# LaserTagSMT.net
KiCad netlist of a schematic drawn in EAGLE
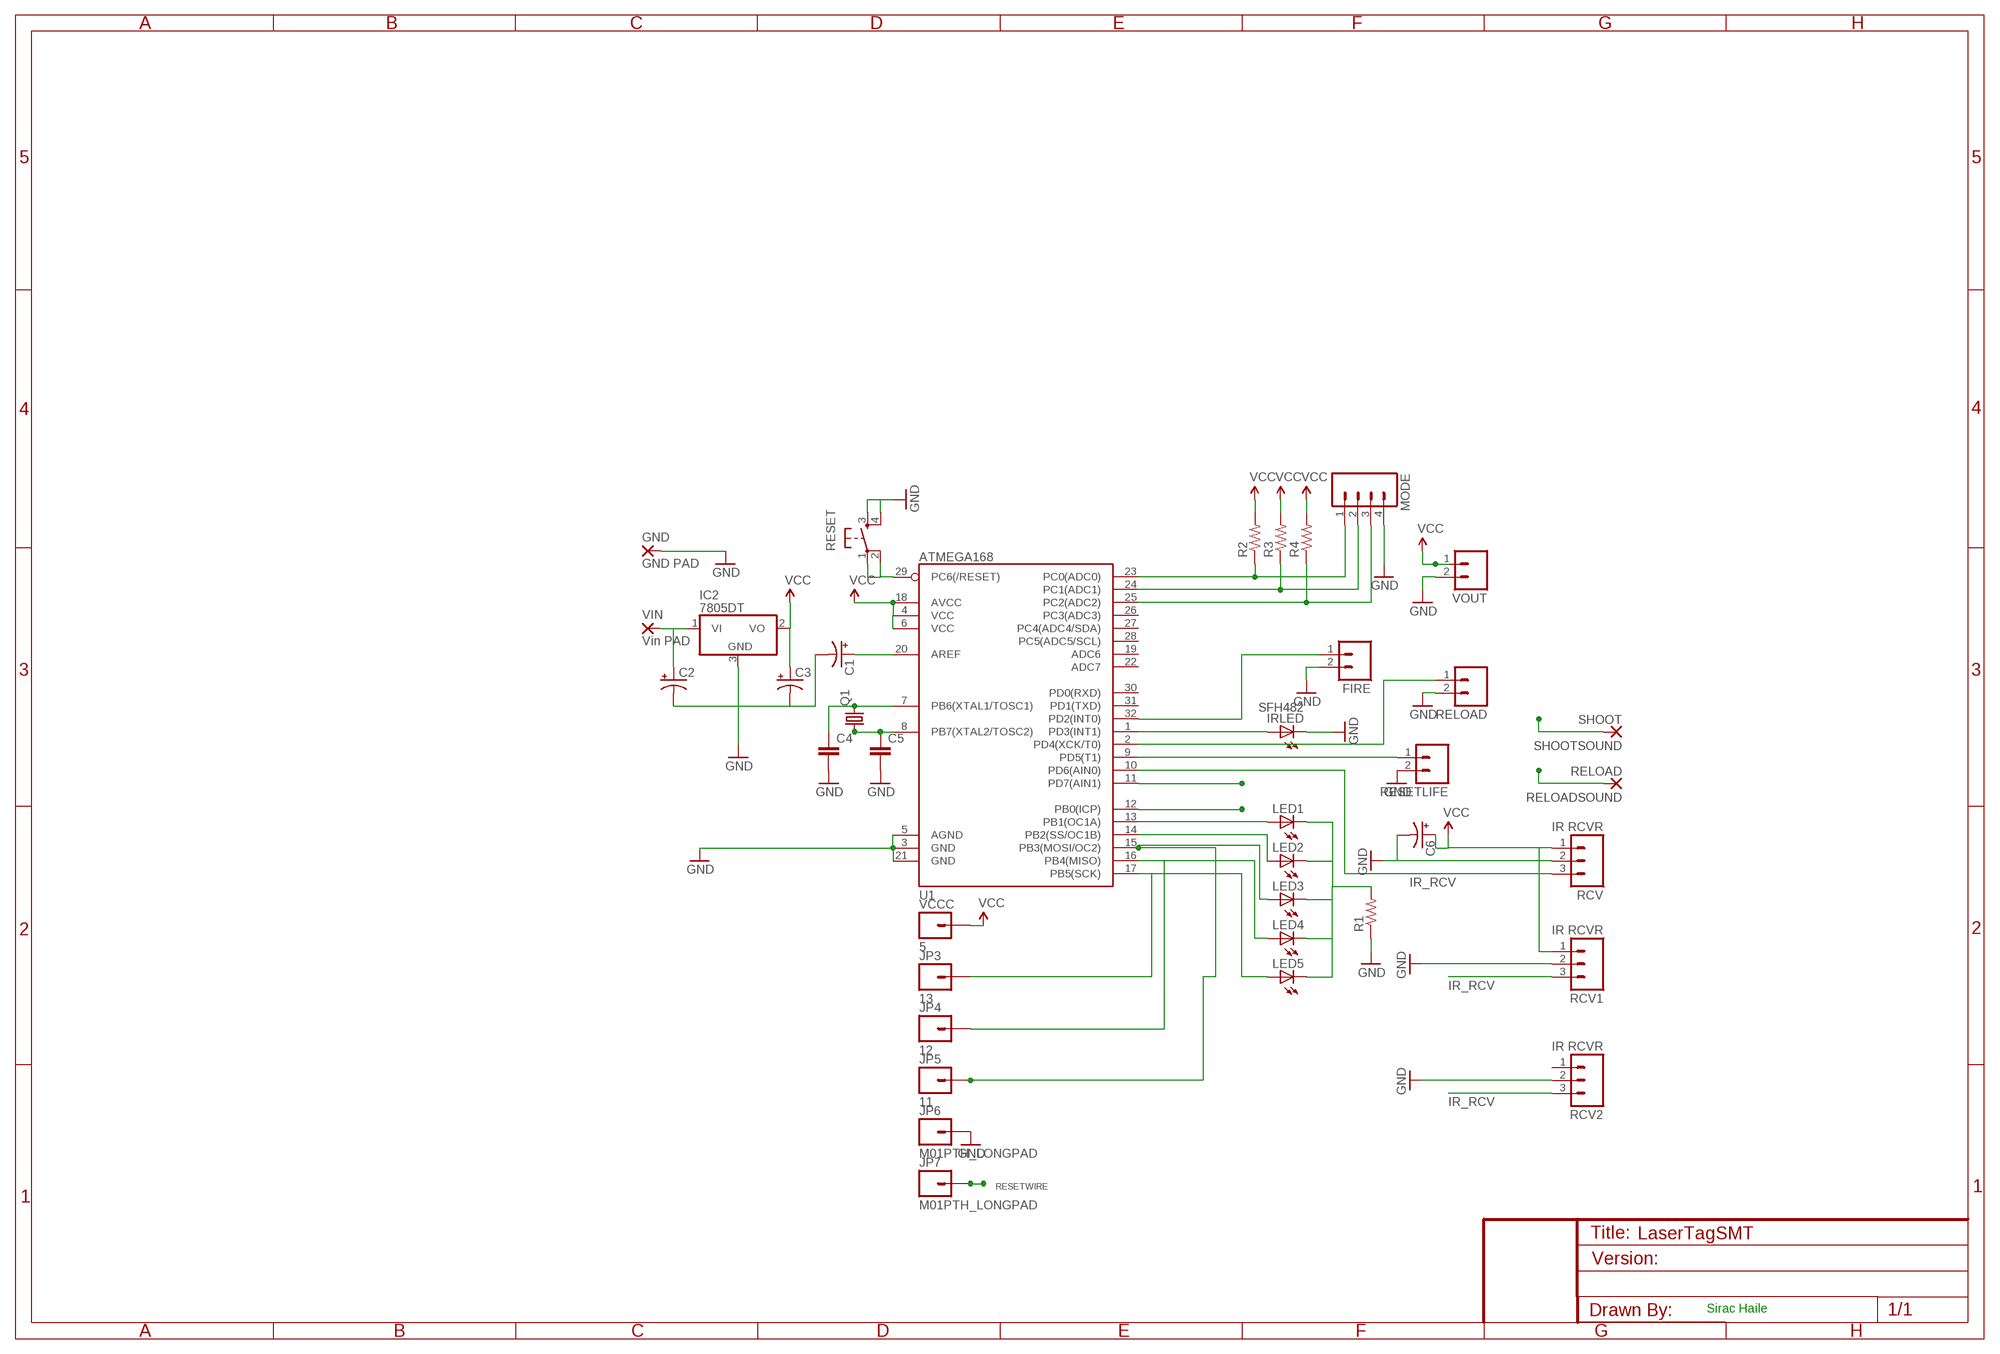
[diagram p0: schematic, sheet 1]

(export (version "E")
  (design (tool "Eeschema 10.0.6"))
  (components
    (comp (ref "C1")
      (value "CAP_POLPTH1")
      (footprint "eagle-import:CPOL-RADIAL-100UF-25V")
      (libsource (lib "eagle-import") (part "CAP_POLPTH1"))
    )
    (comp (ref "C2")
      (value "CAP_POLPTH1")
      (footprint "eagle-import:CPOL-RADIAL-100UF-25V")
      (libsource (lib "eagle-import") (part "CAP_POLPTH1"))
    )
    (comp (ref "C3")
      (value "CAP_POLPTH1")
      (footprint "eagle-import:CPOL-RADIAL-100UF-25V")
      (libsource (lib "eagle-import") (part "CAP_POLPTH1"))
    )
    (comp (ref "C4")
      (value "CAPEZ")
      (footprint "eagle-import:CAP-PTH-SMALLEZ")
      (libsource (lib "eagle-import") (part "CAPEZ"))
    )
    (comp (ref "C5")
      (value "CAPEZ")
      (footprint "eagle-import:CAP-PTH-SMALLEZ")
      (libsource (lib "eagle-import") (part "CAPEZ"))
    )
    (comp (ref "C6")
      (value "CAP_POLPTH1")
      (footprint "eagle-import:CPOL-RADIAL-100UF-25V")
      (libsource (lib "eagle-import") (part "CAP_POLPTH1"))
    )
    (comp (ref "FIRE")
      (value "M02LOCK_LONGPADS")
      (footprint "eagle-import:1X02_LOCK_LONGPADS")
      (libsource (lib "eagle-import") (part "M02LOCK_LONGPADS"))
    )
    (comp (ref "GND")
      (value "GND PAD")
      (footprint "eagle-import:2,54_1,1")
      (libsource (lib "eagle-import") (part "WIREPAD2,54/1,1"))
    )
    (comp (ref "IC2")
      (value "7805DT")
      (footprint "eagle-import:TO252")
      (libsource (lib "eagle-import") (part "78DT05"))
    )
    (comp (ref "IRLED")
      (value "SFH482")
      (footprint "eagle-import:SFH482")
      (libsource (lib "eagle-import") (part "SFH482"))
    )
    (comp (ref "JP3")
      (value "13")
      (footprint "eagle-import:1X01_LONGPAD")
      (libsource (lib "eagle-import") (part "M01PTH_LONGPAD"))
    )
    (comp (ref "JP4")
      (value "12")
      (footprint "eagle-import:1X01_LONGPAD")
      (libsource (lib "eagle-import") (part "M01PTH_LONGPAD"))
    )
    (comp (ref "JP5")
      (value "11")
      (footprint "eagle-import:1X01_LONGPAD")
      (libsource (lib "eagle-import") (part "M01PTH_LONGPAD"))
    )
    (comp (ref "JP6")
      (value "M01PTH_LONGPAD")
      (footprint "eagle-import:1X01_LONGPAD")
      (libsource (lib "eagle-import") (part "M01PTH_LONGPAD"))
    )
    (comp (ref "JP7")
      (value "M01PTH_LONGPAD")
      (footprint "eagle-import:1X01_LONGPAD")
      (libsource (lib "eagle-import") (part "M01PTH_LONGPAD"))
    )
    (comp (ref "LED1")
      (value "LED5MM")
      (footprint "eagle-import:LED5MM")
      (libsource (lib "eagle-import") (part "LED5MM"))
    )
    (comp (ref "LED2")
      (value "LED5MM")
      (footprint "eagle-import:LED5MM")
      (libsource (lib "eagle-import") (part "LED5MM"))
    )
    (comp (ref "LED3")
      (value "LED5MM")
      (footprint "eagle-import:LED5MM")
      (libsource (lib "eagle-import") (part "LED5MM"))
    )
    (comp (ref "LED4")
      (value "LED5MM")
      (footprint "eagle-import:LED5MM")
      (libsource (lib "eagle-import") (part "LED5MM"))
    )
    (comp (ref "LED5")
      (value "LED5MM")
      (footprint "eagle-import:LED5MM")
      (libsource (lib "eagle-import") (part "LED5MM"))
    )
    (comp (ref "MODE")
      (value "M04LONGPADS")
      (footprint "eagle-import:1X04_LONGPADS")
      (libsource (lib "eagle-import") (part "M04LONGPADS"))
    )
    (comp (ref "Q1")
      (value "CRYSTALHC49S")
      (footprint "eagle-import:HC49_S")
      (fields (field (name "OC_FARNELL") "1667008"))
      (libsource (lib "eagle-import") (part "CRYSTALHC49S"))
    )
    (comp (ref "R1")
      (value "RESISTORKIT")
      (footprint "eagle-import:AXIAL-0.3-KIT")
      (libsource (lib "eagle-import") (part "RESISTORKIT"))
    )
    (comp (ref "R2")
      (value "RESISTORPTH-1/6W")
      (footprint "eagle-import:1_6W-RES")
      (libsource (lib "eagle-import") (part "RESISTORPTH-1/6W"))
    )
    (comp (ref "R3")
      (value "RESISTORPTH-1/6W")
      (footprint "eagle-import:1_6W-RES")
      (libsource (lib "eagle-import") (part "RESISTORPTH-1/6W"))
    )
    (comp (ref "R4")
      (value "RESISTORPTH-1/6W")
      (footprint "eagle-import:1_6W-RES")
      (libsource (lib "eagle-import") (part "RESISTORPTH-1/6W"))
    )
    (comp (ref "RCV")
      (value "IR RCVR")
      (footprint "eagle-import:1X03")
      (libsource (lib "eagle-import") (part "M03PTH"))
    )
    (comp (ref "RCV1")
      (value "IR RCVR")
      (footprint "eagle-import:1X03")
      (libsource (lib "eagle-import") (part "M03PTH"))
    )
    (comp (ref "RCV2")
      (value "IR RCVR")
      (footprint "eagle-import:1X03")
      (libsource (lib "eagle-import") (part "M03PTH"))
    )
    (comp (ref "RELOAD")
      (value "M02LOCK_LONGPADS")
      (footprint "eagle-import:1X02_LOCK_LONGPADS")
      (libsource (lib "eagle-import") (part "M02LOCK_LONGPADS"))
    )
    (comp (ref "RELOADSOUND")
      (value "RELOAD")
      (footprint "eagle-import:3,17_1,1")
      (libsource (lib "eagle-import") (part "WIREPAD3,17/1,1"))
    )
    (comp (ref "RESET")
      (value "TAC_SWITCHPTH")
      (footprint "eagle-import:TACTILE-PTH")
      (libsource (lib "eagle-import") (part "TAC_SWITCHPTH"))
    )
    (comp (ref "RESETLIFE")
      (value "M02LOCK_LONGPADS")
      (footprint "eagle-import:1X02_LOCK_LONGPADS")
      (libsource (lib "eagle-import") (part "M02LOCK_LONGPADS"))
    )
    (comp (ref "SHOOTSOUND")
      (value "SHOOT")
      (footprint "eagle-import:3,17_1,1")
      (libsource (lib "eagle-import") (part "WIREPAD3,17/1,1"))
    )
    (comp (ref "U1")
      (value "ATMEGA168")
      (footprint "eagle-import:TQFP32-08")
      (libsource (lib "eagle-import") (part "ATMEGA168"))
    )
    (comp (ref "VCCC")
      (value "5")
      (footprint "eagle-import:1X01_LONGPAD")
      (libsource (lib "eagle-import") (part "M01PTH_LONGPAD"))
    )
    (comp (ref "VIN")
      (value "Vin PAD")
      (footprint "eagle-import:2,54_1,1")
      (libsource (lib "eagle-import") (part "WIREPAD2,54/1,1"))
    )
    (comp (ref "VOUT")
      (value "M02PTH3")
      (footprint "eagle-import:1X02_LONGPADS")
      (libsource (lib "eagle-import") (part "M02PTH3"))
    )
  )
  (nets
    (net (code "1") (name "/IR_RCV") (class "Default")
      (node (ref "RCV") (pin "3") (pinfunction "3_3") (pintype "passive"))
      (node (ref "RCV1") (pin "3") (pinfunction "3_3") (pintype "passive"))
      (node (ref "RCV2") (pin "3") (pinfunction "3_3") (pintype "passive"))
      (node (ref "U1") (pin "10") (pinfunction "PD6(AIN0)_10") (pintype "bidirectional"))
    )
    (net (code "2") (name "/RELOADSOUND") (class "Default")
      (node (ref "RELOADSOUND") (pin "1") (pinfunction "P_1") (pintype "passive"))
      (node (ref "U1") (pin "12") (pinfunction "PB0(ICP)_12") (pintype "bidirectional"))
    )
    (net (code "3") (name "/RESETWIRE") (class "Default")
      (node (ref "JP7") (pin "1") (pinfunction "1_1") (pintype "passive"))
      (node (ref "RESET") (pin "1") (pinfunction "1_1") (pintype "passive"))
      (node (ref "RESET") (pin "2") (pinfunction "2_2") (pintype "passive"))
      (node (ref "U1") (pin "29") (pinfunction "PC6(/RESET)_29") (pintype "bidirectional"))
    )
    (net (code "4") (name "/SHOOTSOUND") (class "Default")
      (node (ref "SHOOTSOUND") (pin "1") (pinfunction "P_1") (pintype "passive"))
      (node (ref "U1") (pin "11") (pinfunction "PD7(AIN1)_11") (pintype "bidirectional"))
    )
    (net (code "5") (name "GND") (class "Default")
      (node (ref "C1") (pin "2") (pinfunction "-_2") (pintype "passive"))
      (node (ref "C2") (pin "2") (pinfunction "-_2") (pintype "passive"))
      (node (ref "C3") (pin "2") (pinfunction "-_2") (pintype "passive"))
      (node (ref "C4") (pin "2") (pinfunction "2_2") (pintype "passive"))
      (node (ref "C5") (pin "2") (pinfunction "2_2") (pintype "passive"))
      (node (ref "C6") (pin "2") (pinfunction "-_2") (pintype "passive"))
      (node (ref "FIRE") (pin "2") (pinfunction "2_2") (pintype "passive"))
      (node (ref "GND") (pin "1") (pinfunction "P_1") (pintype "passive"))
      (node (ref "IC2") (pin "3") (pinfunction "GND_3") (pintype "passive"))
      (node (ref "IRLED") (pin "K") (pinfunction "C_K") (pintype "passive"))
      (node (ref "JP6") (pin "1") (pinfunction "1_1") (pintype "passive"))
      (node (ref "MODE") (pin "4") (pinfunction "4_4") (pintype "passive"))
      (node (ref "R1") (pin "P$1") (pinfunction "1_P$1") (pintype "passive"))
      (node (ref "RCV") (pin "2") (pinfunction "2_2") (pintype "passive"))
      (node (ref "RCV1") (pin "2") (pinfunction "2_2") (pintype "passive"))
      (node (ref "RCV2") (pin "2") (pinfunction "2_2") (pintype "passive"))
      (node (ref "RELOAD") (pin "2") (pinfunction "2_2") (pintype "passive"))
      (node (ref "RESET") (pin "3") (pinfunction "3_3") (pintype "passive"))
      (node (ref "RESET") (pin "4") (pinfunction "4_4") (pintype "passive"))
      (node (ref "RESETLIFE") (pin "2") (pinfunction "2_2") (pintype "passive"))
      (node (ref "U1") (pin "21") (pinfunction "GND_21") (pintype "bidirectional"))
      (node (ref "U1") (pin "3") (pinfunction "GND_3") (pintype "bidirectional"))
      (node (ref "U1") (pin "5") (pinfunction "AGND_5") (pintype "bidirectional"))
      (node (ref "VOUT") (pin "2") (pinfunction "2_2") (pintype "passive"))
    )
    (net (code "6") (name "Net-(C1-+)") (class "Default")
      (node (ref "C1") (pin "1") (pinfunction "+_1") (pintype "passive"))
      (node (ref "U1") (pin "20") (pinfunction "AREF_20") (pintype "bidirectional"))
    )
    (net (code "7") (name "Net-(C2-+)") (class "Default")
      (node (ref "C2") (pin "1") (pinfunction "+_1") (pintype "passive"))
      (node (ref "IC2") (pin "1") (pinfunction "VI_1") (pintype "input"))
      (node (ref "VIN") (pin "1") (pinfunction "P_1") (pintype "passive"))
    )
    (net (code "8") (name "Net-(LED1-C)") (class "Default")
      (node (ref "LED1") (pin "K") (pinfunction "C_K") (pintype "passive"))
      (node (ref "LED2") (pin "K") (pinfunction "C_K") (pintype "passive"))
      (node (ref "LED3") (pin "K") (pinfunction "C_K") (pintype "passive"))
      (node (ref "LED4") (pin "K") (pinfunction "C_K") (pintype "passive"))
      (node (ref "LED5") (pin "K") (pinfunction "C_K") (pintype "passive"))
      (node (ref "R1") (pin "P$2") (pinfunction "2_P$2") (pintype "passive"))
    )
    (net (code "9") (name "Net-(U1-PB1(OC1A))") (class "Default")
      (node (ref "LED1") (pin "A") (pinfunction "A_A") (pintype "passive"))
      (node (ref "U1") (pin "13") (pinfunction "PB1(OC1A)_13") (pintype "bidirectional"))
    )
    (net (code "10") (name "Net-(U1-PB2(SS{slash}OC1B))") (class "Default")
      (node (ref "LED2") (pin "A") (pinfunction "A_A") (pintype "passive"))
      (node (ref "U1") (pin "14") (pinfunction "PB2(SS/OC1B)_14") (pintype "bidirectional"))
    )
    (net (code "11") (name "Net-(U1-PB3(MOSI{slash}OC2))") (class "Default")
      (node (ref "JP5") (pin "1") (pinfunction "1_1") (pintype "passive"))
      (node (ref "LED3") (pin "A") (pinfunction "A_A") (pintype "passive"))
      (node (ref "U1") (pin "15") (pinfunction "PB3(MOSI/OC2)_15") (pintype "bidirectional"))
    )
    (net (code "12") (name "Net-(U1-PB4(MISO))") (class "Default")
      (node (ref "JP4") (pin "1") (pinfunction "1_1") (pintype "passive"))
      (node (ref "LED4") (pin "A") (pinfunction "A_A") (pintype "passive"))
      (node (ref "U1") (pin "16") (pinfunction "PB4(MISO)_16") (pintype "bidirectional"))
    )
    (net (code "13") (name "Net-(U1-PB5(SCK))") (class "Default")
      (node (ref "JP3") (pin "1") (pinfunction "1_1") (pintype "passive"))
      (node (ref "LED5") (pin "A") (pinfunction "A_A") (pintype "passive"))
      (node (ref "U1") (pin "17") (pinfunction "PB5(SCK)_17") (pintype "bidirectional"))
    )
    (net (code "14") (name "Net-(U1-PB6(XTAL1{slash}TOSC1))") (class "Default")
      (node (ref "C4") (pin "1") (pinfunction "1_1") (pintype "passive"))
      (node (ref "Q1") (pin "2") (pinfunction "2_2") (pintype "passive"))
      (node (ref "U1") (pin "7") (pinfunction "PB6(XTAL1/TOSC1)_7") (pintype "bidirectional"))
    )
    (net (code "15") (name "Net-(U1-PB7(XTAL2{slash}TOSC2))") (class "Default")
      (node (ref "C5") (pin "1") (pinfunction "1_1") (pintype "passive"))
      (node (ref "Q1") (pin "1") (pinfunction "1_1") (pintype "passive"))
      (node (ref "U1") (pin "8") (pinfunction "PB7(XTAL2/TOSC2)_8") (pintype "bidirectional"))
    )
    (net (code "16") (name "Net-(U1-PC0(ADC0))") (class "Default")
      (node (ref "MODE") (pin "1") (pinfunction "1_1") (pintype "passive"))
      (node (ref "R2") (pin "1") (pinfunction "1_1") (pintype "passive"))
      (node (ref "U1") (pin "23") (pinfunction "PC0(ADC0)_23") (pintype "bidirectional"))
    )
    (net (code "17") (name "Net-(U1-PC1(ADC1))") (class "Default")
      (node (ref "MODE") (pin "2") (pinfunction "2_2") (pintype "passive"))
      (node (ref "R3") (pin "1") (pinfunction "1_1") (pintype "passive"))
      (node (ref "U1") (pin "24") (pinfunction "PC1(ADC1)_24") (pintype "bidirectional"))
    )
    (net (code "18") (name "Net-(U1-PC2(ADC2))") (class "Default")
      (node (ref "MODE") (pin "3") (pinfunction "3_3") (pintype "passive"))
      (node (ref "R4") (pin "1") (pinfunction "1_1") (pintype "passive"))
      (node (ref "U1") (pin "25") (pinfunction "PC2(ADC2)_25") (pintype "bidirectional"))
    )
    (net (code "19") (name "Net-(U1-PD2(INT0))") (class "Default")
      (node (ref "FIRE") (pin "1") (pinfunction "1_1") (pintype "passive"))
      (node (ref "U1") (pin "32") (pinfunction "PD2(INT0)_32") (pintype "bidirectional"))
    )
    (net (code "20") (name "Net-(U1-PD3(INT1))") (class "Default")
      (node (ref "IRLED") (pin "A") (pinfunction "A_A") (pintype "passive"))
      (node (ref "U1") (pin "1") (pinfunction "PD3(INT1)_1") (pintype "bidirectional"))
    )
    (net (code "21") (name "Net-(U1-PD4(XCK{slash}T0))") (class "Default")
      (node (ref "RELOAD") (pin "1") (pinfunction "1_1") (pintype "passive"))
      (node (ref "U1") (pin "2") (pinfunction "PD4(XCK/T0)_2") (pintype "bidirectional"))
    )
    (net (code "22") (name "Net-(U1-PD5(T1))") (class "Default")
      (node (ref "RESETLIFE") (pin "1") (pinfunction "1_1") (pintype "passive"))
      (node (ref "U1") (pin "9") (pinfunction "PD5(T1)_9") (pintype "bidirectional"))
    )
    (net (code "23") (name "VCC") (class "Default")
      (node (ref "C3") (pin "1") (pinfunction "+_1") (pintype "passive"))
      (node (ref "C6") (pin "1") (pinfunction "+_1") (pintype "passive"))
      (node (ref "IC2") (pin "2") (pinfunction "VO_2") (pintype "passive"))
      (node (ref "R2") (pin "2") (pinfunction "2_2") (pintype "passive"))
      (node (ref "R3") (pin "2") (pinfunction "2_2") (pintype "passive"))
      (node (ref "R4") (pin "2") (pinfunction "2_2") (pintype "passive"))
      (node (ref "RCV") (pin "1") (pinfunction "1_1") (pintype "passive"))
      (node (ref "RCV1") (pin "1") (pinfunction "1_1") (pintype "passive"))
      (node (ref "U1") (pin "18") (pinfunction "AVCC_18") (pintype "bidirectional"))
      (node (ref "U1") (pin "4") (pinfunction "VCC_4") (pintype "bidirectional"))
      (node (ref "U1") (pin "6") (pinfunction "VCC_6") (pintype "bidirectional"))
      (node (ref "VCCC") (pin "1") (pinfunction "1_1") (pintype "passive"))
      (node (ref "VOUT") (pin "1") (pinfunction "1_1") (pintype "passive"))
    )
    (net (code "24") (name "unconnected-(RCV2-Pad1)") (class "Default")
      (node (ref "RCV2") (pin "1") (pinfunction "1_1") (pintype "passive"))
    )
    (net (code "25") (name "unconnected-(U1-ADC6-Pad19)") (class "Default")
      (node (ref "U1") (pin "19") (pinfunction "ADC6_19") (pintype "bidirectional"))
    )
    (net (code "26") (name "unconnected-(U1-ADC7-Pad22)") (class "Default")
      (node (ref "U1") (pin "22") (pinfunction "ADC7_22") (pintype "bidirectional"))
    )
    (net (code "27") (name "unconnected-(U1-PC3(ADC3)-Pad26)") (class "Default")
      (node (ref "U1") (pin "26") (pinfunction "PC3(ADC3)_26") (pintype "bidirectional"))
    )
    (net (code "28") (name "unconnected-(U1-PC4(ADC4{slash}SDA)-Pad27)") (class "Default")
      (node (ref "U1") (pin "27") (pinfunction "PC4(ADC4/SDA)_27") (pintype "bidirectional"))
    )
    (net (code "29") (name "unconnected-(U1-PC5(ADC5{slash}SCL)-Pad28)") (class "Default")
      (node (ref "U1") (pin "28") (pinfunction "PC5(ADC5/SCL)_28") (pintype "bidirectional"))
    )
    (net (code "30") (name "unconnected-(U1-PD0(RXD)-Pad30)") (class "Default")
      (node (ref "U1") (pin "30") (pinfunction "PD0(RXD)_30") (pintype "bidirectional"))
    )
    (net (code "31") (name "unconnected-(U1-PD1(TXD)-Pad31)") (class "Default")
      (node (ref "U1") (pin "31") (pinfunction "PD1(TXD)_31") (pintype "bidirectional"))
    )
  )
)
